# FAT34.net
KiCad netlist of a schematic drawn in Altium Designer
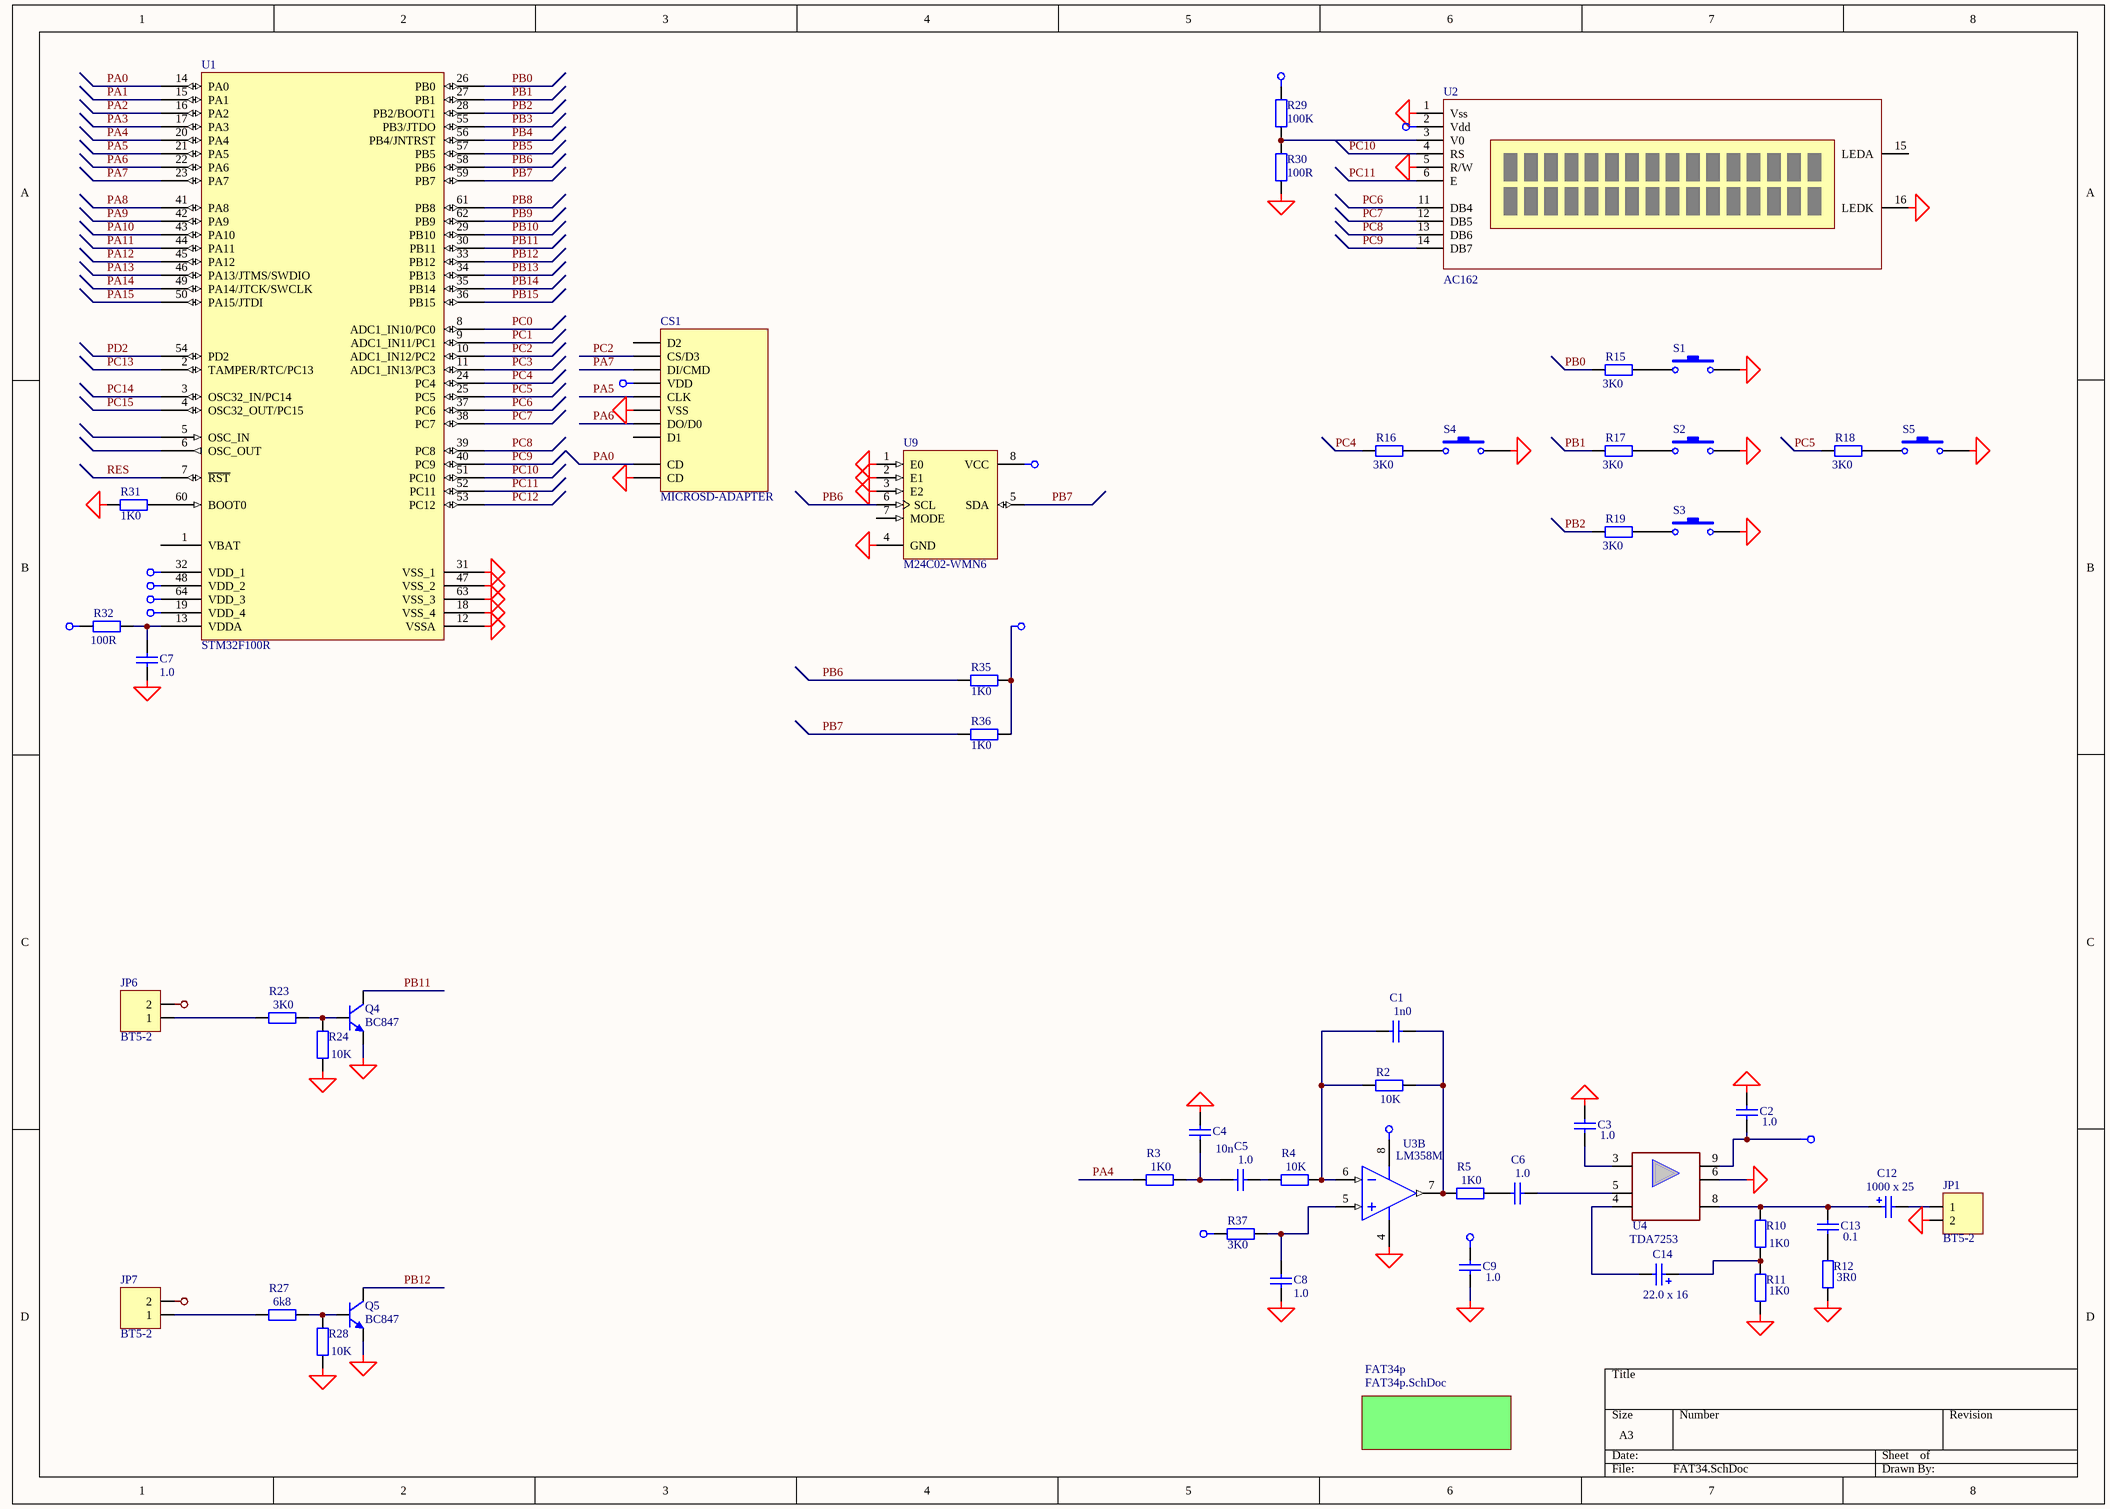
[diagram p0: FAT34.SchDoc]

(export (version "E")
  (design (tool "Eeschema 10.0.6"))
  (components
    (comp (ref "C1")
      (value "1n0")
      (footprint "_1206")
      (description "Capacitor (Semiconductor SIM Model)")
      (fields (field (name "MANUFACTURER") "Generic Components") (field (name "PUBLISHER") "Altium Limited"))
      (libsource (lib "") (part "Cap Semi_1"))
    )
    (comp (ref "C2")
      (value "1.0")
      (footprint "C3216-1206")
      (description "Capacitor (Semiconductor SIM Model)")
      (fields (field (name "MANUFACTURER") "Generic Components") (field (name "PUBLISHER") "Altium Limited"))
      (libsource (lib "") (part "Cap Semi_1"))
    )
    (comp (ref "C3")
      (value "1.0")
      (footprint "C3216-1206")
      (description "Capacitor (Semiconductor SIM Model)")
      (fields (field (name "MANUFACTURER") "Generic Components") (field (name "PUBLISHER") "Altium Limited"))
      (libsource (lib "") (part "Cap Semi_1"))
    )
    (comp (ref "C4")
      (value "10n")
      (footprint "_1206")
      (description "Capacitor (Semiconductor SIM Model)")
      (fields (field (name "MANUFACTURER") "Generic Components") (field (name "PUBLISHER") "Altium Limited"))
      (libsource (lib "Miscellaneous Devices") (part "Cap Semi"))
    )
    (comp (ref "C5")
      (value "1.0")
      (footprint "_1206")
      (description "Capacitor (Semiconductor SIM Model)")
      (fields (field (name "MANUFACTURER") "Generic Components") (field (name "PUBLISHER") "Altium Limited"))
      (libsource (lib "") (part "Cap Semi_1"))
    )
    (comp (ref "C6")
      (value "1.0")
      (footprint "_1206")
      (description "Capacitor (Semiconductor SIM Model)")
      (fields (field (name "MANUFACTURER") "Generic Components") (field (name "PUBLISHER") "Altium Limited"))
      (libsource (lib "") (part "Cap Semi_1"))
    )
    (comp (ref "C7")
      (value "1.0")
      (footprint "_1206")
      (description "Capacitor (Semiconductor SIM Model)")
      (fields (field (name "MANUFACTURER") "Generic Components") (field (name "PUBLISHER") "Altium Limited"))
      (libsource (lib "Miscellaneous Devices") (part "Cap Semi"))
    )
    (comp (ref "C8")
      (value "1.0")
      (footprint "_1206")
      (description "Capacitor (Semiconductor SIM Model)")
      (fields (field (name "MANUFACTURER") "Generic Components") (field (name "PUBLISHER") "Altium Limited"))
      (libsource (lib "Miscellaneous Devices") (part "Cap Semi"))
    )
    (comp (ref "C9")
      (value "1.0")
      (footprint "_1206")
      (description "Capacitor")
      (fields (field (name "MANUFACTURER") "Generic Components") (field (name "PUBLISHER") "Altium Limited"))
      (libsource (lib "BUF") (part "Cap"))
    )
    (comp (ref "C12")
      (value "1000 x 25")
      (footprint "el5")
      (description "Polarized Capacitor (Radial)")
      (fields (field (name "MANUFACTURER") "Generic Components") (field (name "PUBLISHER") "Altium Limited"))
      (libsource (lib "PAL") (part "Cap Pol1"))
    )
    (comp (ref "C13")
      (value "0.1")
      (footprint "C3216-1206")
      (description "Capacitor (Semiconductor SIM Model)")
      (fields (field (name "MANUFACTURER") "Generic Components") (field (name "PUBLISHER") "Altium Limited"))
      (libsource (lib "") (part "Cap Semi_1"))
    )
    (comp (ref "C14")
      (value "22.0 x 16")
      (footprint "el3")
      (description "Polarized Capacitor (Radial)")
      (fields (field (name "MANUFACTURER") "Generic Components") (field (name "PUBLISHER") "Altium Limited"))
      (libsource (lib "PAL") (part "Cap Pol1"))
    )
    (comp (ref "CS1")
      (value "MICROSD-ADAPTER")
      (footprint "microSD_1")
      (libsource (lib "PAL") (part "MICROSD-ADAPTER"))
    )
    (comp (ref "JP1")
      (value "BT5-2")
      (footprint "BT5-2-1")
      (description "Header, 3-Pin")
      (fields (field (name "MANUFACTURER") "Generic Components") (field (name "PUBLISHER") "Altium Limited"))
      (libsource (lib "PAL") (part "BT5-2"))
    )
    (comp (ref "JP6")
      (value "BT5-2")
      (footprint "BT5-2-1")
      (description "Header, 3-Pin")
      (fields (field (name "MANUFACTURER") "Generic Components") (field (name "PUBLISHER") "Altium Limited"))
      (libsource (lib "") (part "BT5-2_1"))
    )
    (comp (ref "JP7")
      (value "BT5-2")
      (footprint "BT5-2-1")
      (description "Header, 3-Pin")
      (fields (field (name "MANUFACTURER") "Generic Components") (field (name "PUBLISHER") "Altium Limited"))
      (libsource (lib "") (part "BT5-2_1"))
    )
    (comp (ref "Q4")
      (value "BC847")
      (footprint "SO-G3")
      (description "General Purpose Transistor NPN Silicon")
      (fields (field (name "MANUFACTURER") "Motorola") (field (name "PUBLISHER") "Altium Limited"))
      (libsource (lib "PAL") (part "BC847ALT1"))
    )
    (comp (ref "Q5")
      (value "BC847")
      (footprint "SO-G3")
      (description "General Purpose Transistor NPN Silicon")
      (fields (field (name "MANUFACTURER") "Motorola") (field (name "PUBLISHER") "Altium Limited"))
      (libsource (lib "PAL") (part "BC847ALT1"))
    )
    (comp (ref "R2")
      (value "10K")
      (footprint "_1206")
      (description "Resistor")
      (fields (field (name "MANUFACTURER") "Generic Components") (field (name "PUBLISHER") "Altium Limited"))
      (libsource (lib "Miscellaneous Devices") (part "Res2"))
    )
    (comp (ref "R3")
      (value "1K0")
      (footprint "_1206")
      (description "Resistor")
      (fields (field (name "MANUFACTURER") "Generic Components") (field (name "PUBLISHER") "Altium Limited"))
      (libsource (lib "Miscellaneous Devices") (part "Res2"))
    )
    (comp (ref "R4")
      (value "10K")
      (footprint "_1206")
      (description "Resistor")
      (fields (field (name "MANUFACTURER") "Generic Components") (field (name "PUBLISHER") "Altium Limited"))
      (libsource (lib "Miscellaneous Devices") (part "Res2"))
    )
    (comp (ref "R5")
      (value "1K0")
      (footprint "_1206")
      (description "Resistor")
      (fields (field (name "MANUFACTURER") "Generic Components") (field (name "PUBLISHER") "Altium Limited"))
      (libsource (lib "") (part "Res2_2"))
    )
    (comp (ref "R10")
      (value "1K0")
      (footprint "_1206")
      (description "Resistor")
      (fields (field (name "MANUFACTURER") "Generic Components") (field (name "PUBLISHER") "Altium Limited"))
      (libsource (lib "PAL") (part "RES"))
    )
    (comp (ref "R11")
      (value "1K0")
      (footprint "_1206")
      (description "Resistor")
      (fields (field (name "MANUFACTURER") "Generic Components") (field (name "PUBLISHER") "Altium Limited"))
      (libsource (lib "PAL") (part "RES"))
    )
    (comp (ref "R12")
      (value "3R0")
      (footprint "_1206")
      (description "Resistor")
      (fields (field (name "MANUFACTURER") "Generic Components") (field (name "PUBLISHER") "Altium Limited"))
      (libsource (lib "PAL") (part "RES"))
    )
    (comp (ref "R15")
      (value "3K0")
      (footprint "_1206")
      (description "Resistor")
      (fields (field (name "MANUFACTURER") "Generic Components") (field (name "PUBLISHER") "Altium Limited"))
      (libsource (lib "") (part "RES_1"))
    )
    (comp (ref "R16")
      (value "3K0")
      (footprint "_1206")
      (description "Resistor")
      (fields (field (name "MANUFACTURER") "Generic Components") (field (name "PUBLISHER") "Altium Limited"))
      (libsource (lib "") (part "RES_1"))
    )
    (comp (ref "R17")
      (value "3K0")
      (footprint "_1206")
      (description "Resistor")
      (fields (field (name "MANUFACTURER") "Generic Components") (field (name "PUBLISHER") "Altium Limited"))
      (libsource (lib "") (part "RES_1"))
    )
    (comp (ref "R18")
      (value "3K0")
      (footprint "_1206")
      (description "Resistor")
      (fields (field (name "MANUFACTURER") "Generic Components") (field (name "PUBLISHER") "Altium Limited"))
      (libsource (lib "") (part "RES_1"))
    )
    (comp (ref "R19")
      (value "3K0")
      (footprint "_1206")
      (description "Resistor")
      (fields (field (name "MANUFACTURER") "Generic Components") (field (name "PUBLISHER") "Altium Limited"))
      (libsource (lib "") (part "RES_1"))
    )
    (comp (ref "R23")
      (value "3K0")
      (footprint "_1206")
      (description "Resistor")
      (fields (field (name "MANUFACTURER") "Generic Components") (field (name "PUBLISHER") "Altium Limited"))
      (libsource (lib "") (part "Res2_1"))
    )
    (comp (ref "R24")
      (value "10K")
      (footprint "_1206")
      (description "Resistor")
      (fields (field (name "MANUFACTURER") "Generic Components") (field (name "PUBLISHER") "Altium Limited"))
      (libsource (lib "Miscellaneous Devices") (part "Res2"))
    )
    (comp (ref "R27")
      (value "6k8")
      (footprint "_1206")
      (description "Resistor")
      (fields (field (name "MANUFACTURER") "Generic Components") (field (name "PUBLISHER") "Altium Limited"))
      (libsource (lib "") (part "Res2_1"))
    )
    (comp (ref "R28")
      (value "10K")
      (footprint "_1206")
      (description "Resistor")
      (fields (field (name "MANUFACTURER") "Generic Components") (field (name "PUBLISHER") "Altium Limited"))
      (libsource (lib "Miscellaneous Devices") (part "Res2"))
    )
    (comp (ref "R29")
      (value "100K")
      (footprint "_1206")
      (description "Resistor")
      (fields (field (name "MANUFACTURER") "Generic Components") (field (name "PUBLISHER") "Altium Limited"))
      (libsource (lib "PAL") (part "RES"))
    )
    (comp (ref "R30")
      (value "100R")
      (footprint "_1206")
      (description "Resistor")
      (fields (field (name "MANUFACTURER") "Generic Components") (field (name "PUBLISHER") "Altium Limited"))
      (libsource (lib "PAL") (part "RES"))
    )
    (comp (ref "R31")
      (value "1K0")
      (footprint "_1206")
      (description "Resistor")
      (fields (field (name "MANUFACTURER") "Generic Components") (field (name "PUBLISHER") "Altium Limited"))
      (libsource (lib "") (part "RES_1"))
    )
    (comp (ref "R32")
      (value "100R")
      (footprint "_1206")
      (description "Resistor")
      (fields (field (name "MANUFACTURER") "Generic Components") (field (name "PUBLISHER") "Altium Limited"))
      (libsource (lib "") (part "Res2_1"))
    )
    (comp (ref "R35")
      (value "1K0")
      (footprint "_1206")
      (description "Resistor")
      (fields (field (name "MANUFACTURER") "Generic Components") (field (name "PUBLISHER") "Altium Limited"))
      (libsource (lib "") (part "RES_1"))
    )
    (comp (ref "R36")
      (value "1K0")
      (footprint "_1206")
      (description "Resistor")
      (fields (field (name "MANUFACTURER") "Generic Components") (field (name "PUBLISHER") "Altium Limited"))
      (libsource (lib "") (part "RES_1"))
    )
    (comp (ref "R37")
      (value "3K0")
      (footprint "_1206")
      (description "Resistor")
      (fields (field (name "MANUFACTURER") "Generic Components") (field (name "PUBLISHER") "Altium Limited"))
      (libsource (lib "") (part "Res2_1"))
    )
    (comp (ref "S1")
      (value "SWT-6")
      (footprint "SWT-6-9")
      (description "Switch")
      (fields (field (name "MANUFACTURER") "Generic Components") (field (name "PUBLISHER") "Altium Limited"))
      (libsource (lib "PAL") (part "SWT-6"))
    )
    (comp (ref "S2")
      (value "SWT-6")
      (footprint "SWT-6-9")
      (description "Switch")
      (fields (field (name "MANUFACTURER") "Generic Components") (field (name "PUBLISHER") "Altium Limited"))
      (libsource (lib "PAL") (part "SWT-6"))
    )
    (comp (ref "S3")
      (value "SWT-6")
      (footprint "SWT-6-9")
      (description "Switch")
      (fields (field (name "MANUFACTURER") "Generic Components") (field (name "PUBLISHER") "Altium Limited"))
      (libsource (lib "PAL") (part "SWT-6"))
    )
    (comp (ref "S4")
      (value "SWT-6")
      (footprint "SWT-6-9")
      (description "Switch")
      (fields (field (name "MANUFACTURER") "Generic Components") (field (name "PUBLISHER") "Altium Limited"))
      (libsource (lib "PAL") (part "SWT-6"))
    )
    (comp (ref "S5")
      (value "SWT-6")
      (footprint "SWT-6-9")
      (description "Switch")
      (fields (field (name "MANUFACTURER") "Generic Components") (field (name "PUBLISHER") "Altium Limited"))
      (libsource (lib "PAL") (part "SWT-6"))
    )
    (comp (ref "U1")
      (value "STM32F100R")
      (footprint "F-QFP10X10-G64/N")
      (description "STM32 ARM-based 32-bit MCU with 64 Kbytes Flash, 64-pin LQFP, Industrial Temperature")
      (fields (field (name "PUBLISHER") "*"))
      (libsource (lib "PAL") (part "STM32F100R"))
    )
    (comp (ref "U2") (value "~") (footprint "AC-162A") (libsource (lib "PAL") (part "AC-162A")))
    (comp (ref "U3")
      (value "LM358M")
      (footprint "SO-G8")
      (description "Low-Power Dual Operational Amplifier")
      (fields
        (field (name "MANUFACTURER") "National Semiconductor")
        (field (name "PUBLISHER") "Altium Limited")
      )
      (libsource (lib "NSC Operational Amplifier") (part "LM358M"))
    )
    (comp (ref "U4") (value "TDA7253") (footprint "Clipwatt11") (libsource (lib "PAL") (part "TDA7253")))
    (comp (ref "U9")
      (value "M24C02-WMN6")
      (footprint "SO-G8/E2.9")
      (description "Serial 1K (128 x 8) EEPROM")
      (fields (field (name "MANUFACTURER") "ST-Microelectronics") (field (name "PUBLISHER") "Altium Limited"))
      (libsource (lib "ST Memory EEPROM Serial") (part "ST24C01M6"))
    )
  )
  (nets
    (net (code "1") (name "+3v3") (class "Default")
      (node (ref "CS1") (pin "4") (pinfunction "VDD_4") (pintype "passive"))
      (node (ref "R32") (pin "2") (pinfunction "2_2") (pintype "passive"))
      (node (ref "R35") (pin "2") (pinfunction "2_2") (pintype "passive"))
      (node (ref "R36") (pin "2") (pinfunction "2_2") (pintype "passive"))
      (node (ref "R37") (pin "2") (pinfunction "2_2") (pintype "passive"))
      (node (ref "U1") (pin "19") (pinfunction "VDD_4_19") (pintype "power_in"))
      (node (ref "U1") (pin "32") (pinfunction "VDD_1_32") (pintype "power_in"))
      (node (ref "U1") (pin "48") (pinfunction "VDD_2_48") (pintype "power_in"))
      (node (ref "U1") (pin "64") (pinfunction "VDD_3_64") (pintype "power_in"))
      (node (ref "U9") (pin "8") (pinfunction "VCC_8") (pintype "power_in"))
    )
    (net (code "2") (name "+5v") (class "Default")
      (node (ref "JP6") (pin "2") (pinfunction "2_2") (pintype "passive"))
      (node (ref "R29") (pin "2") (pinfunction "2_2") (pintype "passive"))
      (node (ref "U2") (pin "2") (pinfunction "Vdd_2") (pintype "passive"))
    )
    (net (code "3") (name "+12v") (class "Default")
      (node (ref "C2") (pin "1") (pinfunction "1_1") (pintype "passive"))
      (node (ref "C9") (pin "2") (pinfunction "2_2") (pintype "passive"))
      (node (ref "JP7") (pin "2") (pinfunction "2_2") (pintype "passive"))
      (node (ref "U3") (pin "8") (pinfunction "V+_8") (pintype "power_in"))
      (node (ref "U4") (pin "9") (pintype "passive"))
    )
    (net (code "4") (name "/PA0") (class "Default")
      (node (ref "CS1") (pin "9") (pinfunction "CD_9") (pintype "passive"))
      (node (ref "U1") (pin "14") (pinfunction "PA0_14") (pintype "bidirectional"))
    )
    (net (code "5") (name "/PA1") (class "Default")
      (node (ref "U1") (pin "15") (pinfunction "PA1_15") (pintype "bidirectional"))
    )
    (net (code "6") (name "/PA2") (class "Default")
      (node (ref "U1") (pin "16") (pinfunction "PA2_16") (pintype "bidirectional"))
    )
    (net (code "7") (name "/PA3") (class "Default")
      (node (ref "U1") (pin "17") (pinfunction "PA3_17") (pintype "bidirectional"))
    )
    (net (code "8") (name "/PA4") (class "Default")
      (node (ref "R3") (pin "2") (pinfunction "2_2") (pintype "passive"))
      (node (ref "U1") (pin "20") (pinfunction "PA4_20") (pintype "bidirectional"))
    )
    (net (code "9") (name "/PA5") (class "Default")
      (node (ref "CS1") (pin "5") (pinfunction "CLK_5") (pintype "passive"))
      (node (ref "U1") (pin "21") (pinfunction "PA5_21") (pintype "bidirectional"))
    )
    (net (code "10") (name "/PA6") (class "Default")
      (node (ref "CS1") (pin "7") (pinfunction "DO/D0_7") (pintype "passive"))
      (node (ref "U1") (pin "22") (pinfunction "PA6_22") (pintype "bidirectional"))
    )
    (net (code "11") (name "/PA7") (class "Default")
      (node (ref "CS1") (pin "3") (pinfunction "DI/CMD_3") (pintype "passive"))
      (node (ref "U1") (pin "23") (pinfunction "PA7_23") (pintype "bidirectional"))
    )
    (net (code "12") (name "/PA8") (class "Default")
      (node (ref "U1") (pin "41") (pinfunction "PA8_41") (pintype "bidirectional"))
    )
    (net (code "13") (name "/PA9") (class "Default")
      (node (ref "U1") (pin "42") (pinfunction "PA9_42") (pintype "bidirectional"))
    )
    (net (code "14") (name "/PA10") (class "Default")
      (node (ref "U1") (pin "43") (pinfunction "PA10_43") (pintype "bidirectional"))
    )
    (net (code "15") (name "/PA11") (class "Default")
      (node (ref "U1") (pin "44") (pinfunction "PA11_44") (pintype "bidirectional"))
    )
    (net (code "16") (name "/PA12") (class "Default")
      (node (ref "U1") (pin "45") (pinfunction "PA12_45") (pintype "bidirectional"))
    )
    (net (code "17") (name "/PA13") (class "Default")
      (node (ref "U1") (pin "46") (pinfunction "PA13/JTMS/SWDIO_46") (pintype "bidirectional"))
    )
    (net (code "18") (name "/PA14") (class "Default")
      (node (ref "U1") (pin "49") (pinfunction "PA14/JTCK/SWCLK_49") (pintype "bidirectional"))
    )
    (net (code "19") (name "/PA15") (class "Default")
      (node (ref "U1") (pin "50") (pinfunction "PA15/JTDI_50") (pintype "bidirectional"))
    )
    (net (code "20") (name "/PB0") (class "Default")
      (node (ref "R15") (pin "1") (pinfunction "1_1") (pintype "passive"))
      (node (ref "U1") (pin "26") (pinfunction "PB0_26") (pintype "bidirectional"))
    )
    (net (code "21") (name "/PB1") (class "Default")
      (node (ref "R17") (pin "1") (pinfunction "1_1") (pintype "passive"))
      (node (ref "U1") (pin "27") (pinfunction "PB1_27") (pintype "bidirectional"))
    )
    (net (code "22") (name "/PB2") (class "Default")
      (node (ref "R19") (pin "1") (pinfunction "1_1") (pintype "passive"))
      (node (ref "U1") (pin "28") (pinfunction "PB2/BOOT1_28") (pintype "bidirectional"))
    )
    (net (code "23") (name "/PB3") (class "Default")
      (node (ref "U1") (pin "55") (pinfunction "PB3/JTDO_55") (pintype "bidirectional"))
    )
    (net (code "24") (name "/PB4") (class "Default")
      (node (ref "U1") (pin "56") (pinfunction "PB4/JNTRST_56") (pintype "bidirectional"))
    )
    (net (code "25") (name "/PB5") (class "Default")
      (node (ref "U1") (pin "57") (pinfunction "PB5_57") (pintype "bidirectional"))
    )
    (net (code "26") (name "/PB6") (class "Default")
      (node (ref "R35") (pin "1") (pinfunction "1_1") (pintype "passive"))
      (node (ref "U1") (pin "58") (pinfunction "PB6_58") (pintype "bidirectional"))
      (node (ref "U9") (pin "6") (pinfunction "SCL_6") (pintype "input"))
    )
    (net (code "27") (name "/PB7") (class "Default")
      (node (ref "R36") (pin "1") (pinfunction "1_1") (pintype "passive"))
      (node (ref "U1") (pin "59") (pinfunction "PB7_59") (pintype "bidirectional"))
      (node (ref "U9") (pin "5") (pinfunction "SDA_5") (pintype "bidirectional"))
    )
    (net (code "28") (name "/PB8") (class "Default")
      (node (ref "U1") (pin "61") (pinfunction "PB8_61") (pintype "bidirectional"))
    )
    (net (code "29") (name "/PB9") (class "Default")
      (node (ref "U1") (pin "62") (pinfunction "PB9_62") (pintype "bidirectional"))
    )
    (net (code "30") (name "/PB10") (class "Default")
      (node (ref "U1") (pin "29") (pinfunction "PB10_29") (pintype "bidirectional"))
    )
    (net (code "31") (name "/PB11") (class "Default")
      (node (ref "Q4") (pin "3") (pinfunction "C_3") (pintype "passive"))
      (node (ref "U1") (pin "30") (pinfunction "PB11_30") (pintype "bidirectional"))
    )
    (net (code "32") (name "/PB12") (class "Default")
      (node (ref "Q5") (pin "3") (pinfunction "C_3") (pintype "passive"))
      (node (ref "U1") (pin "33") (pinfunction "PB12_33") (pintype "bidirectional"))
    )
    (net (code "33") (name "/PB13") (class "Default")
      (node (ref "U1") (pin "34") (pinfunction "PB13_34") (pintype "bidirectional"))
    )
    (net (code "34") (name "/PB14") (class "Default")
      (node (ref "U1") (pin "35") (pinfunction "PB14_35") (pintype "bidirectional"))
    )
    (net (code "35") (name "/PB15") (class "Default")
      (node (ref "U1") (pin "36") (pinfunction "PB15_36") (pintype "bidirectional"))
    )
    (net (code "36") (name "/PC0") (class "Default")
      (node (ref "U1") (pin "8") (pinfunction "ADC1_IN10/PC0_8") (pintype "bidirectional"))
    )
    (net (code "37") (name "/PC1") (class "Default")
      (node (ref "U1") (pin "9") (pinfunction "ADC1_IN11/PC1_9") (pintype "bidirectional"))
    )
    (net (code "38") (name "/PC2") (class "Default")
      (node (ref "CS1") (pin "2") (pinfunction "CS/D3_2") (pintype "passive"))
      (node (ref "U1") (pin "10") (pinfunction "ADC1_IN12/PC2_10") (pintype "bidirectional"))
    )
    (net (code "39") (name "/PC3") (class "Default")
      (node (ref "U1") (pin "11") (pinfunction "ADC1_IN13/PC3_11") (pintype "bidirectional"))
    )
    (net (code "40") (name "/PC4") (class "Default")
      (node (ref "R16") (pin "1") (pinfunction "1_1") (pintype "passive"))
      (node (ref "U1") (pin "24") (pinfunction "PC4_24") (pintype "bidirectional"))
    )
    (net (code "41") (name "/PC5") (class "Default")
      (node (ref "R18") (pin "1") (pinfunction "1_1") (pintype "passive"))
      (node (ref "U1") (pin "25") (pinfunction "PC5_25") (pintype "bidirectional"))
    )
    (net (code "42") (name "/PC6") (class "Default")
      (node (ref "U1") (pin "37") (pinfunction "PC6_37") (pintype "bidirectional"))
      (node (ref "U2") (pin "11") (pinfunction "DB4_11") (pintype "passive"))
    )
    (net (code "43") (name "/PC7") (class "Default")
      (node (ref "U1") (pin "38") (pinfunction "PC7_38") (pintype "bidirectional"))
      (node (ref "U2") (pin "12") (pinfunction "DB5_12") (pintype "passive"))
    )
    (net (code "44") (name "/PC8") (class "Default")
      (node (ref "U1") (pin "39") (pinfunction "PC8_39") (pintype "bidirectional"))
      (node (ref "U2") (pin "13") (pinfunction "DB6_13") (pintype "passive"))
    )
    (net (code "45") (name "/PC9") (class "Default")
      (node (ref "U1") (pin "40") (pinfunction "PC9_40") (pintype "bidirectional"))
      (node (ref "U2") (pin "14") (pinfunction "DB7_14") (pintype "passive"))
    )
    (net (code "46") (name "/PC10") (class "Default")
      (node (ref "U1") (pin "51") (pinfunction "PC10_51") (pintype "bidirectional"))
      (node (ref "U2") (pin "4") (pinfunction "RS_4") (pintype "passive"))
    )
    (net (code "47") (name "/PC11") (class "Default")
      (node (ref "U1") (pin "52") (pinfunction "PC11_52") (pintype "bidirectional"))
      (node (ref "U2") (pin "6") (pinfunction "E_6") (pintype "passive"))
    )
    (net (code "48") (name "/PC12") (class "Default")
      (node (ref "U1") (pin "53") (pinfunction "PC12_53") (pintype "bidirectional"))
    )
    (net (code "49") (name "/PC13") (class "Default")
      (node (ref "U1") (pin "2") (pinfunction "TAMPER/RTC/PC13_2") (pintype "bidirectional"))
    )
    (net (code "50") (name "/PC14") (class "Default")
      (node (ref "U1") (pin "3") (pinfunction "OSC32_IN/PC14_3") (pintype "bidirectional"))
    )
    (net (code "51") (name "/PC15") (class "Default")
      (node (ref "U1") (pin "4") (pinfunction "OSC32_OUT/PC15_4") (pintype "bidirectional"))
    )
    (net (code "52") (name "/PD2") (class "Default")
      (node (ref "U1") (pin "54") (pinfunction "PD2_54") (pintype "bidirectional"))
    )
    (net (code "53") (name "/RES") (class "Default")
      (node (ref "U1") (pin "7") (pinfunction "~{RST}_7") (pintype "bidirectional"))
    )
    (net (code "54") (name "GND") (class "Default")
      (node (ref "C2") (pin "2") (pinfunction "2_2") (pintype "passive"))
      (node (ref "C3") (pin "2") (pinfunction "2_2") (pintype "passive"))
      (node (ref "C4") (pin "2") (pinfunction "2_2") (pintype "passive"))
      (node (ref "C7") (pin "2") (pinfunction "2_2") (pintype "passive"))
      (node (ref "C8") (pin "2") (pinfunction "2_2") (pintype "passive"))
      (node (ref "C9") (pin "1") (pinfunction "1_1") (pintype "passive"))
      (node (ref "CS1") (pin "10") (pinfunction "CD_10") (pintype "passive"))
      (node (ref "CS1") (pin "6") (pinfunction "VSS_6") (pintype "passive"))
      (node (ref "JP1") (pin "2") (pinfunction "2_2") (pintype "passive"))
      (node (ref "Q4") (pin "2") (pinfunction "E_2") (pintype "passive"))
      (node (ref "Q5") (pin "2") (pinfunction "E_2") (pintype "passive"))
      (node (ref "R11") (pin "1") (pinfunction "1_1") (pintype "passive"))
      (node (ref "R12") (pin "1") (pinfunction "1_1") (pintype "passive"))
      (node (ref "R24") (pin "2") (pinfunction "2_2") (pintype "passive"))
      (node (ref "R28") (pin "2") (pinfunction "2_2") (pintype "passive"))
      (node (ref "R30") (pin "1") (pinfunction "1_1") (pintype "passive"))
      (node (ref "R31") (pin "1") (pinfunction "1_1") (pintype "passive"))
      (node (ref "S1") (pin "2") (pinfunction "2_2") (pintype "passive"))
      (node (ref "S2") (pin "2") (pinfunction "2_2") (pintype "passive"))
      (node (ref "S3") (pin "2") (pinfunction "2_2") (pintype "passive"))
      (node (ref "S4") (pin "2") (pinfunction "2_2") (pintype "passive"))
      (node (ref "S5") (pin "2") (pinfunction "2_2") (pintype "passive"))
      (node (ref "U1") (pin "12") (pinfunction "VSSA_12") (pintype "power_in"))
      (node (ref "U1") (pin "18") (pinfunction "VSS_4_18") (pintype "power_in"))
      (node (ref "U1") (pin "31") (pinfunction "VSS_1_31") (pintype "power_in"))
      (node (ref "U1") (pin "47") (pinfunction "VSS_2_47") (pintype "power_in"))
      (node (ref "U1") (pin "63") (pinfunction "VSS_3_63") (pintype "power_in"))
      (node (ref "U2") (pin "1") (pinfunction "Vss_1") (pintype "passive"))
      (node (ref "U2") (pin "16") (pinfunction "LEDK_16") (pintype "passive"))
      (node (ref "U2") (pin "5") (pinfunction "R/W_5") (pintype "passive"))
      (node (ref "U3") (pin "4") (pinfunction "GND_4") (pintype "power_in"))
      (node (ref "U4") (pin "6") (pintype "passive"))
      (node (ref "U9") (pin "1") (pinfunction "E0_1") (pintype "input"))
      (node (ref "U9") (pin "2") (pinfunction "E1_2") (pintype "input"))
      (node (ref "U9") (pin "3") (pinfunction "E2_3") (pintype "input"))
      (node (ref "U9") (pin "4") (pinfunction "GND_4") (pintype "power_in"))
    )
    (net (code "55") (name "Net-(C4-Pad1)") (class "Default")
      (node (ref "C4") (pin "1") (pinfunction "1_1") (pintype "passive"))
      (node (ref "C5") (pin "1") (pinfunction "1_1") (pintype "passive"))
      (node (ref "R3") (pin "1") (pinfunction "1_1") (pintype "passive"))
    )
    (net (code "56") (name "Net-(C5-Pad2)") (class "Default")
      (node (ref "C5") (pin "2") (pinfunction "2_2") (pintype "passive"))
      (node (ref "R4") (pin "2") (pinfunction "2_2") (pintype "passive"))
    )
    (net (code "57") (name "Net-(C6-Pad1)") (class "Default")
      (node (ref "C6") (pin "1") (pinfunction "1_1") (pintype "passive"))
      (node (ref "R5") (pin "2") (pinfunction "2_2") (pintype "passive"))
    )
    (net (code "58") (name "Net-(C12-Pad1)") (class "Default")
      (node (ref "C12") (pin "1") (pinfunction "1_1") (pintype "passive"))
      (node (ref "C13") (pin "2") (pinfunction "2_2") (pintype "passive"))
      (node (ref "R10") (pin "2") (pinfunction "2_2") (pintype "passive"))
      (node (ref "U4") (pin "8") (pintype "passive"))
    )
    (net (code "59") (name "Net-(C12-Pad2)") (class "Default")
      (node (ref "C12") (pin "2") (pinfunction "2_2") (pintype "passive"))
      (node (ref "JP1") (pin "1") (pinfunction "1_1") (pintype "passive"))
    )
    (net (code "60") (name "Net-(C13-Pad1)") (class "Default")
      (node (ref "C13") (pin "1") (pinfunction "1_1") (pintype "passive"))
      (node (ref "R12") (pin "2") (pinfunction "2_2") (pintype "passive"))
    )
    (net (code "61") (name "Net-(C14-Pad1)") (class "Default")
      (node (ref "C14") (pin "1") (pinfunction "1_1") (pintype "passive"))
      (node (ref "R10") (pin "1") (pinfunction "1_1") (pintype "passive"))
      (node (ref "R11") (pin "2") (pinfunction "2_2") (pintype "passive"))
    )
    (net (code "62") (name "Net-(C14-Pad2)") (class "Default")
      (node (ref "C14") (pin "2") (pinfunction "2_2") (pintype "passive"))
      (node (ref "U4") (pin "4") (pintype "passive"))
    )
    (net (code "63") (name "Net-(JP6-Pad1)") (class "Default")
      (node (ref "JP6") (pin "1") (pinfunction "1_1") (pintype "passive"))
      (node (ref "R23") (pin "2") (pinfunction "2_2") (pintype "passive"))
    )
    (net (code "64") (name "Net-(JP7-Pad1)") (class "Default")
      (node (ref "JP7") (pin "1") (pinfunction "1_1") (pintype "passive"))
      (node (ref "R27") (pin "2") (pinfunction "2_2") (pintype "passive"))
    )
    (net (code "65") (name "Net-(Q4-B)") (class "Default")
      (node (ref "Q4") (pin "1") (pinfunction "B_1") (pintype "passive"))
      (node (ref "R23") (pin "1") (pinfunction "1_1") (pintype "passive"))
      (node (ref "R24") (pin "1") (pinfunction "1_1") (pintype "passive"))
    )
    (net (code "66") (name "Net-(Q5-B)") (class "Default")
      (node (ref "Q5") (pin "1") (pinfunction "B_1") (pintype "passive"))
      (node (ref "R27") (pin "1") (pinfunction "1_1") (pintype "passive"))
      (node (ref "R28") (pin "1") (pinfunction "1_1") (pintype "passive"))
    )
    (net (code "67") (name "Net-(R15-Pad2)") (class "Default")
      (node (ref "R15") (pin "2") (pinfunction "2_2") (pintype "passive"))
      (node (ref "S1") (pin "1") (pinfunction "1_1") (pintype "passive"))
    )
    (net (code "68") (name "Net-(R16-Pad2)") (class "Default")
      (node (ref "R16") (pin "2") (pinfunction "2_2") (pintype "passive"))
      (node (ref "S4") (pin "1") (pinfunction "1_1") (pintype "passive"))
    )
    (net (code "69") (name "Net-(R17-Pad2)") (class "Default")
      (node (ref "R17") (pin "2") (pinfunction "2_2") (pintype "passive"))
      (node (ref "S2") (pin "1") (pinfunction "1_1") (pintype "passive"))
    )
    (net (code "70") (name "Net-(R18-Pad2)") (class "Default")
      (node (ref "R18") (pin "2") (pinfunction "2_2") (pintype "passive"))
      (node (ref "S5") (pin "1") (pinfunction "1_1") (pintype "passive"))
    )
    (net (code "71") (name "Net-(R19-Pad2)") (class "Default")
      (node (ref "R19") (pin "2") (pinfunction "2_2") (pintype "passive"))
      (node (ref "S3") (pin "1") (pinfunction "1_1") (pintype "passive"))
    )
    (net (code "72") (name "Net-(U1-BOOT0)") (class "Default")
      (node (ref "R31") (pin "2") (pinfunction "2_2") (pintype "passive"))
      (node (ref "U1") (pin "60") (pinfunction "BOOT0_60") (pintype "input"))
    )
    (net (code "73") (name "Net-(U1-VDDA)") (class "Default")
      (node (ref "C7") (pin "1") (pinfunction "1_1") (pintype "passive"))
      (node (ref "R32") (pin "1") (pinfunction "1_1") (pintype "passive"))
      (node (ref "U1") (pin "13") (pinfunction "VDDA_13") (pintype "power_in"))
    )
    (net (code "74") (name "Net-(U2-V0)") (class "Default")
      (node (ref "R29") (pin "1") (pinfunction "1_1") (pintype "passive"))
      (node (ref "R30") (pin "2") (pinfunction "2_2") (pintype "passive"))
      (node (ref "U2") (pin "3") (pinfunction "V0_3") (pintype "passive"))
    )
    (net (code "75") (name "Net-(U3B-IN+)") (class "Default")
      (node (ref "C8") (pin "1") (pinfunction "1_1") (pintype "passive"))
      (node (ref "R37") (pin "1") (pinfunction "1_1") (pintype "passive"))
      (node (ref "U3") (pin "5") (pinfunction "IN+_5") (pintype "input"))
    )
    (net (code "76") (name "Net-(U3B-IN-)") (class "Default")
      (node (ref "C1") (pin "2") (pinfunction "2_2") (pintype "passive"))
      (node (ref "R2") (pin "2") (pinfunction "2_2") (pintype "passive"))
      (node (ref "R4") (pin "1") (pinfunction "1_1") (pintype "passive"))
      (node (ref "U3") (pin "6") (pinfunction "IN-_6") (pintype "input"))
    )
    (net (code "77") (name "Net-(U3B-OUT)") (class "Default")
      (node (ref "C1") (pin "1") (pinfunction "1_1") (pintype "passive"))
      (node (ref "R2") (pin "1") (pinfunction "1_1") (pintype "passive"))
      (node (ref "R5") (pin "1") (pinfunction "1_1") (pintype "passive"))
      (node (ref "U3") (pin "7") (pinfunction "OUT_7") (pintype "output"))
    )
    (net (code "78") (name "Net-(U4-+)") (class "Default")
      (node (ref "C6") (pin "2") (pinfunction "2_2") (pintype "passive"))
      (node (ref "U4") (pin "5") (pinfunction "+_5") (pintype "passive"))
    )
    (net (code "79") (name "Net-(U4-MUTE)") (class "Default")
      (node (ref "C3") (pin "1") (pinfunction "1_1") (pintype "passive"))
      (node (ref "U4") (pin "3") (pinfunction "MUTE_3") (pintype "passive"))
    )
    (net (code "80") (name "unconnected-(CS1-D1-Pad8)") (class "Default")
      (node (ref "CS1") (pin "8") (pinfunction "D1_8") (pintype "passive"))
    )
    (net (code "81") (name "unconnected-(CS1-D2-Pad1)") (class "Default")
      (node (ref "CS1") (pin "1") (pinfunction "D2_1") (pintype "passive"))
    )
    (net (code "82") (name "unconnected-(U1-OSC_IN-Pad5)") (class "Default")
      (node (ref "U1") (pin "5") (pinfunction "OSC_IN_5") (pintype "input"))
    )
    (net (code "83") (name "unconnected-(U1-OSC_OUT-Pad6)") (class "Default")
      (node (ref "U1") (pin "6") (pinfunction "OSC_OUT_6") (pintype "output"))
    )
    (net (code "84") (name "unconnected-(U1-VBAT-Pad1)") (class "Default")
      (node (ref "U1") (pin "1") (pinfunction "VBAT_1") (pintype "power_in"))
    )
    (net (code "85") (name "unconnected-(U2-LEDA-Pad15)") (class "Default")
      (node (ref "U2") (pin "15") (pinfunction "LEDA_15") (pintype "passive"))
    )
    (net (code "86") (name "unconnected-(U9-MODE-Pad7)") (class "Default")
      (node (ref "U9") (pin "7") (pinfunction "MODE_7") (pintype "input"))
    )
  )
)
